# board.net
KiCad netlist of a schematic drawn in EAGLE
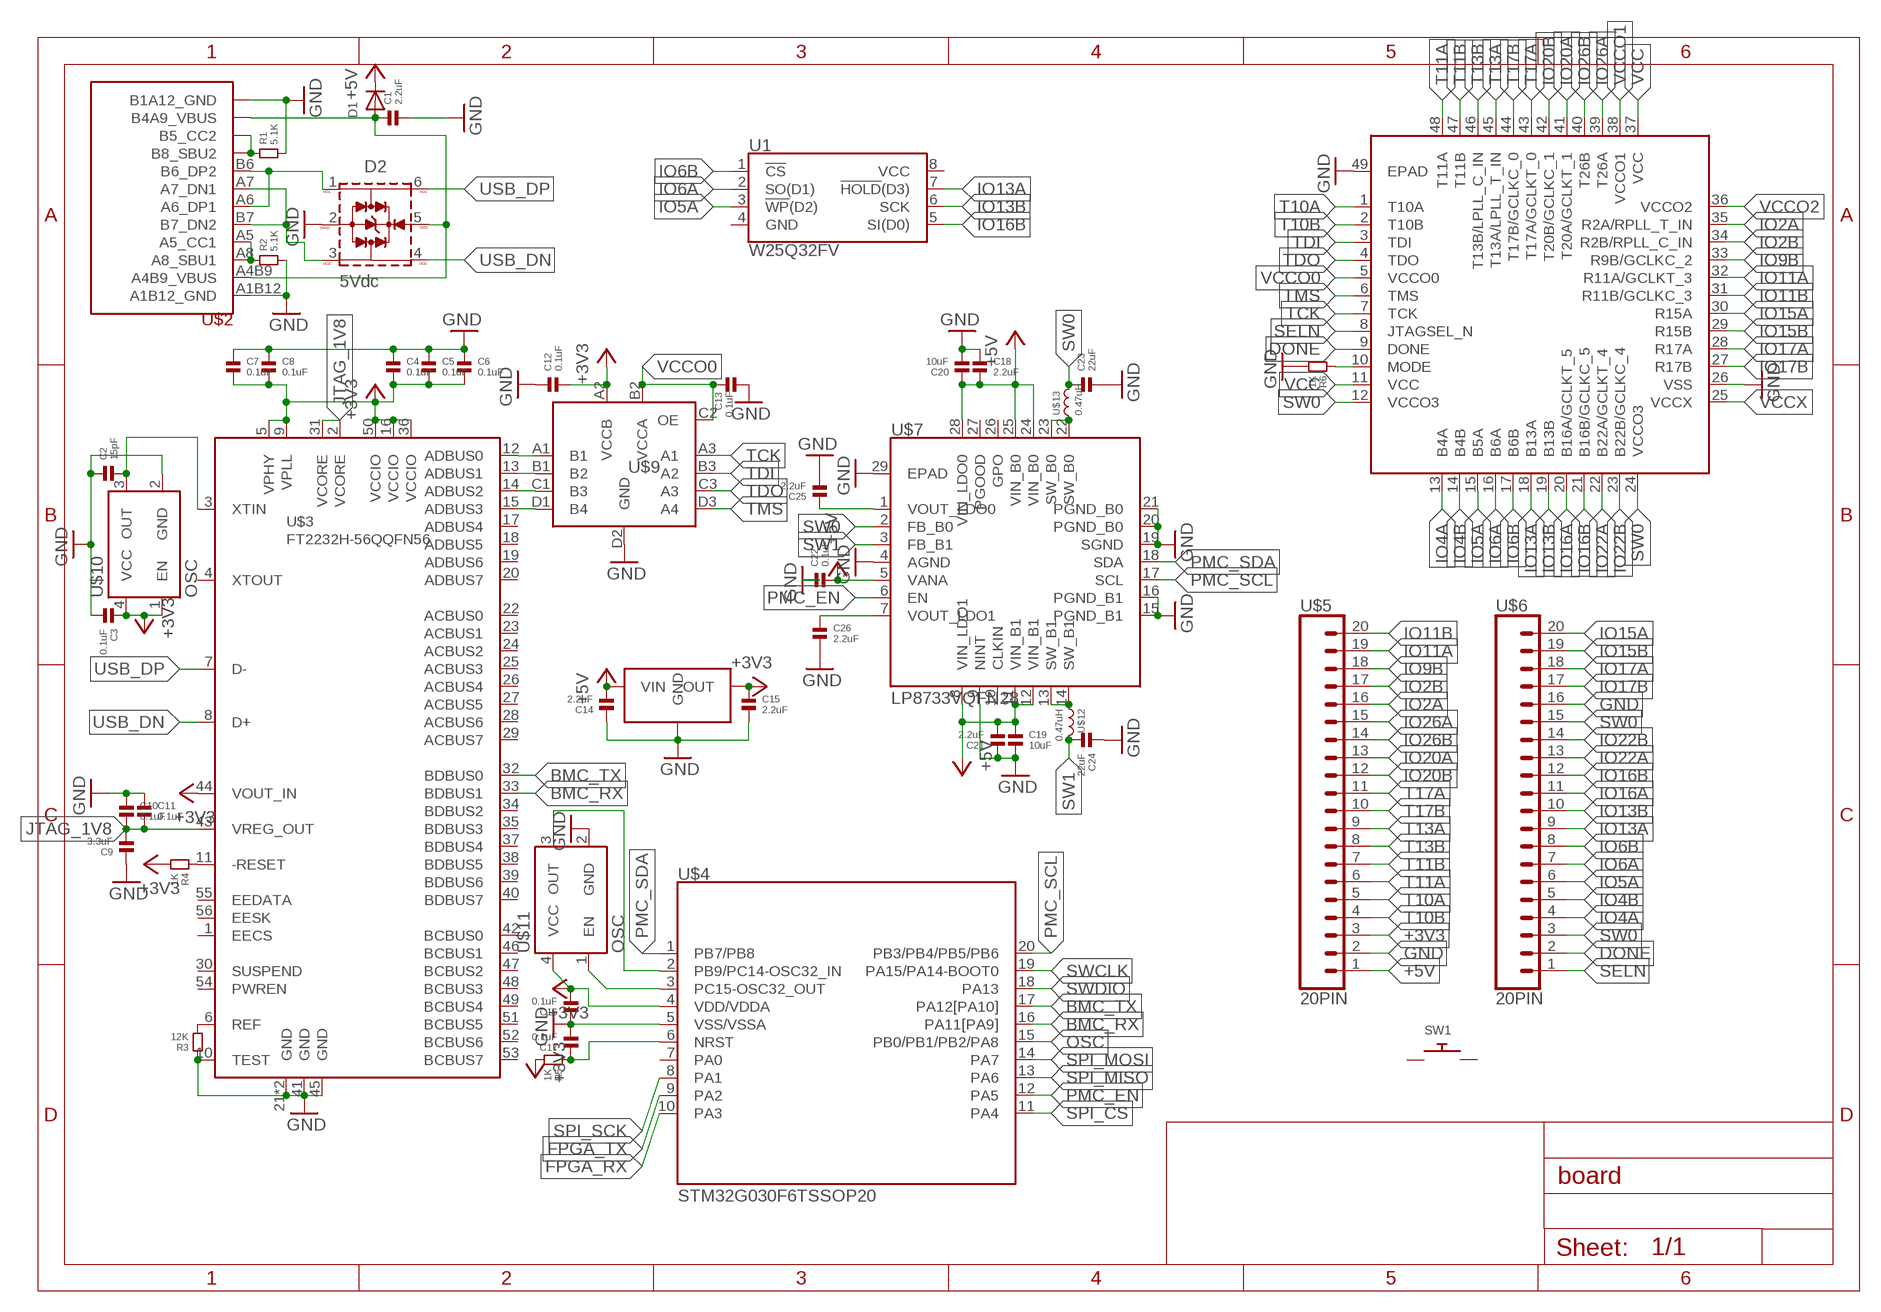
[diagram p0: schematic, sheet 1]

(export (version "E")
  (design (tool "Eeschema 10.0.6"))
  (components
    (comp (ref "C1")
      (value "2.2uF")
      (footprint "eagle-import:0603_CAP")
      (libsource (lib "eagle-import") (part "CAPACITOR0603"))
    )
    (comp (ref "C2")
      (value "15pF")
      (footprint "eagle-import:0402_CAP")
      (libsource (lib "eagle-import") (part "CAPACITOR"))
    )
    (comp (ref "C3")
      (value "0.1uF")
      (footprint "eagle-import:0402_CAP")
      (libsource (lib "eagle-import") (part "CAPACITOR"))
    )
    (comp (ref "C4")
      (value "0.1uF")
      (footprint "eagle-import:0402_CAP")
      (libsource (lib "eagle-import") (part "CAPACITOR"))
    )
    (comp (ref "C5")
      (value "0.1uF")
      (footprint "eagle-import:0402_CAP")
      (libsource (lib "eagle-import") (part "CAPACITOR"))
    )
    (comp (ref "C6")
      (value "0.1uF")
      (footprint "eagle-import:0402_CAP")
      (libsource (lib "eagle-import") (part "CAPACITOR"))
    )
    (comp (ref "C7")
      (value "0.1uF")
      (footprint "eagle-import:0402_CAP")
      (libsource (lib "eagle-import") (part "CAPACITOR"))
    )
    (comp (ref "C8")
      (value "0.1uF")
      (footprint "eagle-import:0402_CAP")
      (libsource (lib "eagle-import") (part "CAPACITOR"))
    )
    (comp (ref "C9")
      (value "3.3uF")
      (footprint "eagle-import:0603_CAP")
      (libsource (lib "eagle-import") (part "CAPACITOR0603"))
    )
    (comp (ref "C10")
      (value "0.1uF")
      (footprint "eagle-import:0402_CAP")
      (libsource (lib "eagle-import") (part "CAPACITOR"))
    )
    (comp (ref "C11")
      (value "0.1uF")
      (footprint "eagle-import:0402_CAP")
      (libsource (lib "eagle-import") (part "CAPACITOR"))
    )
    (comp (ref "C12")
      (value "0.1uF")
      (footprint "eagle-import:0402_CAP")
      (libsource (lib "eagle-import") (part "CAPACITOR"))
    )
    (comp (ref "C13")
      (value "0.1uF")
      (footprint "eagle-import:0402_CAP")
      (libsource (lib "eagle-import") (part "CAPACITOR"))
    )
    (comp (ref "C14")
      (value "2.2uF")
      (footprint "eagle-import:0603_CAP")
      (libsource (lib "eagle-import") (part "CAPACITOR0603"))
    )
    (comp (ref "C15")
      (value "2.2uF")
      (footprint "eagle-import:0603_CAP")
      (libsource (lib "eagle-import") (part "CAPACITOR0603"))
    )
    (comp (ref "C16")
      (value "0.1uF")
      (footprint "eagle-import:0402_CAP")
      (libsource (lib "eagle-import") (part "CAPACITOR"))
    )
    (comp (ref "C17")
      (value "0.1uF")
      (footprint "eagle-import:0402_CAP")
      (libsource (lib "eagle-import") (part "CAPACITOR"))
    )
    (comp (ref "C18")
      (value "2.2uF")
      (footprint "eagle-import:0603_CAP")
      (libsource (lib "eagle-import") (part "CAPACITOR0603"))
    )
    (comp (ref "C19")
      (value "10uF")
      (footprint "eagle-import:0805_CAP")
      (libsource (lib "eagle-import") (part "CAPACITOR0805"))
    )
    (comp (ref "C20")
      (value "10uF")
      (footprint "eagle-import:0805_CAP")
      (libsource (lib "eagle-import") (part "CAPACITOR0805"))
    )
    (comp (ref "C21")
      (value "2.2uF")
      (footprint "eagle-import:0603_CAP")
      (libsource (lib "eagle-import") (part "CAPACITOR0603"))
    )
    (comp (ref "C22")
      (value "0.1uF")
      (footprint "eagle-import:0402_CAP")
      (libsource (lib "eagle-import") (part "CAPACITOR"))
    )
    (comp (ref "C23")
      (value "22uF")
      (footprint "eagle-import:0805_CAP")
      (libsource (lib "eagle-import") (part "CAPACITOR0805"))
    )
    (comp (ref "C24")
      (value "22uF")
      (footprint "eagle-import:0805_CAP")
      (libsource (lib "eagle-import") (part "CAPACITOR0805"))
    )
    (comp (ref "C25")
      (value "2.2uF")
      (footprint "eagle-import:0603_CAP")
      (libsource (lib "eagle-import") (part "CAPACITOR0603"))
    )
    (comp (ref "C26")
      (value "2.2uF")
      (footprint "eagle-import:0603_CAP")
      (libsource (lib "eagle-import") (part "CAPACITOR0603"))
    )
    (comp (ref "D1")
      (value "DIODESOD-323F")
      (footprint "eagle-import:SOD-323F")
      (libsource (lib "eagle-import") (part "DIODESOD-323F"))
    )
    (comp (ref "D2")
      (value "5Vdc")
      (footprint "eagle-import:WE-TVS_SOT23-6L")
      (libsource (lib "eagle-import") (part "WE-TVS-HS_SOT23-6L_82400102"))
    )
    (comp (ref "R1")
      (value "5.1K")
      (footprint "eagle-import:0402")
      (libsource (lib "eagle-import") (part "RESISTOR.0402"))
    )
    (comp (ref "R2")
      (value "5.1K")
      (footprint "eagle-import:0402")
      (libsource (lib "eagle-import") (part "RESISTOR.0402"))
    )
    (comp (ref "R3")
      (value "12K")
      (footprint "eagle-import:0402")
      (libsource (lib "eagle-import") (part "RESISTOR.0402"))
    )
    (comp (ref "R4")
      (value "1K")
      (footprint "eagle-import:0402")
      (libsource (lib "eagle-import") (part "RESISTOR.0402"))
    )
    (comp (ref "R5")
      (value "1K")
      (footprint "eagle-import:0402")
      (libsource (lib "eagle-import") (part "RESISTOR.0402"))
    )
    (comp (ref "R6")
      (value "1K")
      (footprint "eagle-import:0402")
      (libsource (lib "eagle-import") (part "RESISTOR.0402"))
    )
    (comp (ref "SW1")
      (value "SWITCH_PUSHBUTTONC&K_KSS")
      (footprint "eagle-import:BTN_CK_KSS")
      (libsource (lib "eagle-import") (part "SWITCH_PUSHBUTTONC&K_KSS"))
    )
    (comp (ref "U$1")
      (value "GW1NSR-4CQN48P")
      (footprint "eagle-import:QFN40P600X600X80-49T420N")
      (libsource (lib "eagle-import") (part "GW1NSR-4CQN48P"))
    )
    (comp (ref "U$2")
      (value "TYPEC")
      (footprint "eagle-import:TYPE-C-31-M-12")
      (libsource (lib "eagle-import") (part "TYPEC"))
    )
    (comp (ref "U$3")
      (value "FT2232H-56QQFN56")
      (footprint "eagle-import:QFN50P800X800X90-57T595N")
      (libsource (lib "eagle-import") (part "FT2232H-56QQFN56"))
    )
    (comp (ref "U$4")
      (value "STM32G030F6TSSOP20")
      (footprint "eagle-import:SOP65P640X120-20N")
      (libsource (lib "eagle-import") (part "STM32G030F6TSSOP20"))
    )
    (comp (ref "U$5")
      (value "20PIN")
      (footprint "eagle-import:HDRV20W64P254_1X20_5080X254X838B")
      (libsource (lib "eagle-import") (part "120PIN"))
    )
    (comp (ref "U$6")
      (value "20PIN")
      (footprint "eagle-import:HDRV20W64P254_1X20_5080X254X838B")
      (libsource (lib "eagle-import") (part "120PIN"))
    )
    (comp (ref "U$7")
      (value "LP8733VQFN28")
      (footprint "eagle-import:QFN50P500X500X100-29T340N")
      (libsource (lib "eagle-import") (part "LP8733VQFN28"))
    )
    (comp (ref "U$8")
      (value "XC6206")
      (footprint "eagle-import:SOT95P280X125-3")
      (libsource (lib "eagle-import") (part "XC6206"))
    )
    (comp (ref "U$9")
      (value "TXS0104EYZTR")
      (footprint "eagle-import:BGA12C50P3X4_186X136X62N")
      (libsource (lib "eagle-import") (part "TXS0104EYZTR"))
    )
    (comp (ref "U$10")
      (value "OSC")
      (footprint "eagle-import:OSCCC200X160X85N")
      (libsource (lib "eagle-import") (part "OSC"))
    )
    (comp (ref "U$11")
      (value "OSC")
      (footprint "eagle-import:OSCCC200X160X85N")
      (libsource (lib "eagle-import") (part "OSC"))
    )
    (comp (ref "U$12")
      (value "0.47uH")
      (footprint "eagle-import:INDM2621X120")
      (libsource (lib "eagle-import") (part "SPH252012H1R5MT"))
    )
    (comp (ref "U$13")
      (value "0.47uH")
      (footprint "eagle-import:INDM2621X120")
      (libsource (lib "eagle-import") (part "SPH252012H1R5MT"))
    )
    (comp (ref "U1")
      (value "W25Q32FV")
      (footprint "eagle-import:SOIC-8")
      (libsource (lib "eagle-import") (part "GD25LQ128DVIG"))
    )
  )
  (nets
    (net (code "1") (name "+3V3") (class "Default")
      (node (ref "C12") (pin "2") (pinfunction "2_2") (pintype "bidirectional"))
      (node (ref "C15") (pin "1") (pinfunction "1_1") (pintype "bidirectional"))
      (node (ref "C16") (pin "2") (pinfunction "2_2") (pintype "bidirectional"))
      (node (ref "C3") (pin "1") (pinfunction "1_1") (pintype "bidirectional"))
      (node (ref "C4") (pin "2") (pinfunction "2_2") (pintype "bidirectional"))
      (node (ref "C5") (pin "2") (pinfunction "2_2") (pintype "bidirectional"))
      (node (ref "C6") (pin "2") (pinfunction "2_2") (pintype "bidirectional"))
      (node (ref "C7") (pin "2") (pinfunction "2_2") (pintype "bidirectional"))
      (node (ref "C8") (pin "2") (pinfunction "2_2") (pintype "bidirectional"))
      (node (ref "R4") (pin "2") (pinfunction "2_2") (pintype "bidirectional"))
      (node (ref "R5") (pin "2") (pinfunction "2_2") (pintype "bidirectional"))
      (node (ref "U$10") (pin "1") (pinfunction "EN_1") (pintype "bidirectional"))
      (node (ref "U$10") (pin "4") (pinfunction "VCC_4") (pintype "bidirectional"))
      (node (ref "U$11") (pin "4") (pinfunction "VCC_4") (pintype "bidirectional"))
      (node (ref "U$3") (pin "16") (pinfunction "VCCIO_16") (pintype "bidirectional"))
      (node (ref "U$3") (pin "36") (pinfunction "VCCIO_36") (pintype "bidirectional"))
      (node (ref "U$3") (pin "44") (pinfunction "VOUT_IN_44") (pintype "bidirectional"))
      (node (ref "U$3") (pin "5") (pinfunction "VPHY_5") (pintype "bidirectional"))
      (node (ref "U$3") (pin "50") (pinfunction "VCCIO_50") (pintype "bidirectional"))
      (node (ref "U$3") (pin "9") (pinfunction "VPLL_9") (pintype "bidirectional"))
      (node (ref "U$4") (pin "4") (pinfunction "VDD/VDDA_4") (pintype "bidirectional"))
      (node (ref "U$5") (pin "3") (pinfunction "3_3") (pintype "passive"))
      (node (ref "U$8") (pin "2") (pinfunction "OUT_2") (pintype "bidirectional"))
      (node (ref "U$9") (pin "A2") (pinfunction "VCCB_A2") (pintype "bidirectional"))
    )
    (net (code "2") (name "+5V") (class "Default")
      (node (ref "C14") (pin "2") (pinfunction "2_2") (pintype "bidirectional"))
      (node (ref "C18") (pin "2") (pinfunction "2_2") (pintype "bidirectional"))
      (node (ref "C19") (pin "1") (pinfunction "1_1") (pintype "bidirectional"))
      (node (ref "C20") (pin "1") (pinfunction "1_1") (pintype "bidirectional"))
      (node (ref "C21") (pin "2") (pinfunction "2_2") (pintype "bidirectional"))
      (node (ref "C22") (pin "2") (pinfunction "2_2") (pintype "bidirectional"))
      (node (ref "D1") (pin "C") (pinfunction "C_C") (pintype "passive"))
      (node (ref "U$5") (pin "1") (pinfunction "1_1") (pintype "passive"))
      (node (ref "U$7") (pin "11") (pinfunction "VIN_B1_11") (pintype "bidirectional"))
      (node (ref "U$7") (pin "12") (pinfunction "VIN_B1_12") (pintype "bidirectional"))
      (node (ref "U$7") (pin "24") (pinfunction "VIN_B0_24") (pintype "bidirectional"))
      (node (ref "U$7") (pin "25") (pinfunction "VIN_B0_25") (pintype "bidirectional"))
      (node (ref "U$7") (pin "28") (pinfunction "VIN_LDO0_28") (pintype "bidirectional"))
      (node (ref "U$7") (pin "5") (pinfunction "VANA_5") (pintype "bidirectional"))
      (node (ref "U$7") (pin "8") (pinfunction "VIN_LDO1_8") (pintype "bidirectional"))
      (node (ref "U$8") (pin "3") (pinfunction "VIN_3") (pintype "bidirectional"))
    )
    (net (code "3") (name "BMC_RX") (class "Default")
      (node (ref "U$3") (pin "33") (pinfunction "BDBUS1_33") (pintype "bidirectional"))
      (node (ref "U$4") (pin "16") (pinfunction "PA11[PA9]_16") (pintype "bidirectional"))
    )
    (net (code "4") (name "BMC_TX") (class "Default")
      (node (ref "U$3") (pin "32") (pinfunction "BDBUS0_32") (pintype "bidirectional"))
      (node (ref "U$4") (pin "17") (pinfunction "PA12[PA10]_17") (pintype "bidirectional"))
    )
    (net (code "5") (name "DONE") (class "Default")
      (node (ref "U$1") (pin "9") (pinfunction "DONE_9") (pintype "bidirectional"))
      (node (ref "U$6") (pin "2") (pinfunction "2_2") (pintype "passive"))
    )
    (net (code "6") (name "FPGA_RX") (class "Default")
      (node (ref "U$4") (pin "10") (pinfunction "PA3_10") (pintype "bidirectional"))
    )
    (net (code "7") (name "FPGA_TX") (class "Default")
      (node (ref "U$4") (pin "9") (pinfunction "PA2_9") (pintype "bidirectional"))
    )
    (net (code "8") (name "GND") (class "Default")
      (node (ref "C1") (pin "2") (pinfunction "2_2") (pintype "bidirectional"))
      (node (ref "C10") (pin "1") (pinfunction "1_1") (pintype "bidirectional"))
      (node (ref "C11") (pin "1") (pinfunction "1_1") (pintype "bidirectional"))
      (node (ref "C12") (pin "1") (pinfunction "1_1") (pintype "bidirectional"))
      (node (ref "C13") (pin "2") (pinfunction "2_2") (pintype "bidirectional"))
      (node (ref "C14") (pin "1") (pinfunction "1_1") (pintype "bidirectional"))
      (node (ref "C15") (pin "2") (pinfunction "2_2") (pintype "bidirectional"))
      (node (ref "C16") (pin "1") (pinfunction "1_1") (pintype "bidirectional"))
      (node (ref "C17") (pin "2") (pinfunction "2_2") (pintype "bidirectional"))
      (node (ref "C18") (pin "1") (pinfunction "1_1") (pintype "bidirectional"))
      (node (ref "C19") (pin "2") (pinfunction "2_2") (pintype "bidirectional"))
      (node (ref "C2") (pin "1") (pinfunction "1_1") (pintype "bidirectional"))
      (node (ref "C20") (pin "2") (pinfunction "2_2") (pintype "bidirectional"))
      (node (ref "C21") (pin "1") (pinfunction "1_1") (pintype "bidirectional"))
      (node (ref "C22") (pin "1") (pinfunction "1_1") (pintype "bidirectional"))
      (node (ref "C23") (pin "2") (pinfunction "2_2") (pintype "bidirectional"))
      (node (ref "C24") (pin "1") (pinfunction "1_1") (pintype "bidirectional"))
      (node (ref "C25") (pin "2") (pinfunction "2_2") (pintype "bidirectional"))
      (node (ref "C26") (pin "2") (pinfunction "2_2") (pintype "bidirectional"))
      (node (ref "C3") (pin "2") (pinfunction "2_2") (pintype "bidirectional"))
      (node (ref "C4") (pin "1") (pinfunction "1_1") (pintype "bidirectional"))
      (node (ref "C5") (pin "1") (pinfunction "1_1") (pintype "bidirectional"))
      (node (ref "C6") (pin "1") (pinfunction "1_1") (pintype "bidirectional"))
      (node (ref "C7") (pin "1") (pinfunction "1_1") (pintype "bidirectional"))
      (node (ref "C8") (pin "1") (pinfunction "1_1") (pintype "bidirectional"))
      (node (ref "C9") (pin "1") (pinfunction "1_1") (pintype "bidirectional"))
      (node (ref "D2") (pin "2") (pinfunction "GND_2") (pintype "passive"))
      (node (ref "R1") (pin "2") (pinfunction "2_2") (pintype "bidirectional"))
      (node (ref "R2") (pin "2") (pinfunction "2_2") (pintype "bidirectional"))
      (node (ref "R3") (pin "1") (pinfunction "1_1") (pintype "bidirectional"))
      (node (ref "R6") (pin "2") (pinfunction "2_2") (pintype "bidirectional"))
      (node (ref "U$1") (pin "26") (pinfunction "VSS_26") (pintype "bidirectional"))
      (node (ref "U$1") (pin "49") (pinfunction "EPAD_49") (pintype "bidirectional"))
      (node (ref "U$10") (pin "2") (pinfunction "GND_2") (pintype "bidirectional"))
      (node (ref "U$11") (pin "2") (pinfunction "GND_2") (pintype "bidirectional"))
      (node (ref "U$2") (pin "A1B12") (pinfunction "A1B12_GND_A1B12") (pintype "bidirectional"))
      (node (ref "U$2") (pin "B1A12") (pinfunction "B1A12_GND_B1A12") (pintype "bidirectional"))
      (node (ref "U$3") (pin "10") (pinfunction "TEST_10") (pintype "bidirectional"))
      (node (ref "U$3") (pin "21") (pinfunction "GND_21") (pintype "power_in"))
      (node (ref "U$3") (pin "41") (pinfunction "GND_41") (pintype "power_in"))
      (node (ref "U$3") (pin "45") (pinfunction "GND_45") (pintype "power_in"))
      (node (ref "U$3") (pin "57") (pinfunction "GND_57") (pintype "power_in"))
      (node (ref "U$4") (pin "5") (pinfunction "VSS/VSSA_5") (pintype "bidirectional"))
      (node (ref "U$5") (pin "2") (pinfunction "2_2") (pintype "passive"))
      (node (ref "U$6") (pin "16") (pinfunction "16_16") (pintype "passive"))
      (node (ref "U$7") (pin "15") (pinfunction "PGND_B1_15") (pintype "bidirectional"))
      (node (ref "U$7") (pin "16") (pinfunction "PGND_B1_16") (pintype "bidirectional"))
      (node (ref "U$7") (pin "19") (pinfunction "SGND_19") (pintype "bidirectional"))
      (node (ref "U$7") (pin "20") (pinfunction "PGND_B0_20") (pintype "bidirectional"))
      (node (ref "U$7") (pin "21") (pinfunction "PGND_B0_21") (pintype "bidirectional"))
      (node (ref "U$7") (pin "29") (pinfunction "EPAD_29") (pintype "bidirectional"))
      (node (ref "U$7") (pin "4") (pinfunction "AGND_4") (pintype "bidirectional"))
      (node (ref "U$7") (pin "9") (pinfunction "NINT_9") (pintype "bidirectional"))
      (node (ref "U$8") (pin "1") (pinfunction "GND_1") (pintype "bidirectional"))
      (node (ref "U$9") (pin "D2") (pinfunction "GND_D2") (pintype "bidirectional"))
    )
    (net (code "9") (name "IO2A") (class "Default")
      (node (ref "U$1") (pin "35") (pinfunction "R2A/RPLL_T_IN_35") (pintype "bidirectional"))
      (node (ref "U$5") (pin "16") (pinfunction "16_16") (pintype "passive"))
    )
    (net (code "10") (name "IO2B") (class "Default")
      (node (ref "U$1") (pin "34") (pinfunction "R2B/RPLL_C_IN_34") (pintype "bidirectional"))
      (node (ref "U$5") (pin "17") (pinfunction "17_17") (pintype "passive"))
    )
    (net (code "11") (name "IO4A") (class "Default")
      (node (ref "U$1") (pin "13") (pinfunction "B4A_13") (pintype "bidirectional"))
      (node (ref "U$6") (pin "4") (pinfunction "4_4") (pintype "passive"))
    )
    (net (code "12") (name "IO4B") (class "Default")
      (node (ref "U$1") (pin "14") (pinfunction "B4B_14") (pintype "bidirectional"))
      (node (ref "U$6") (pin "5") (pinfunction "5_5") (pintype "passive"))
    )
    (net (code "13") (name "IO5A") (class "Default")
      (node (ref "U$1") (pin "15") (pinfunction "B5A_15") (pintype "bidirectional"))
      (node (ref "U$6") (pin "6") (pinfunction "6_6") (pintype "passive"))
      (node (ref "U1") (pin "3") (pinfunction "~{WP}(D2)_3") (pintype "bidirectional"))
    )
    (net (code "14") (name "IO6A") (class "Default")
      (node (ref "U$1") (pin "16") (pinfunction "B6A_16") (pintype "bidirectional"))
      (node (ref "U$6") (pin "7") (pinfunction "7_7") (pintype "passive"))
      (node (ref "U1") (pin "2") (pinfunction "SO(D1)_2") (pintype "bidirectional"))
    )
    (net (code "15") (name "IO6B") (class "Default")
      (node (ref "U$1") (pin "17") (pinfunction "B6B_17") (pintype "bidirectional"))
      (node (ref "U$6") (pin "8") (pinfunction "8_8") (pintype "passive"))
      (node (ref "U1") (pin "1") (pinfunction "~{CS}_1") (pintype "bidirectional"))
    )
    (net (code "16") (name "IO9B") (class "Default")
      (node (ref "U$1") (pin "33") (pinfunction "R9B/GCLKC_2_33") (pintype "bidirectional"))
      (node (ref "U$5") (pin "18") (pinfunction "18_18") (pintype "passive"))
    )
    (net (code "17") (name "IO11A") (class "Default")
      (node (ref "U$1") (pin "32") (pinfunction "R11A/GCLKT_3_32") (pintype "bidirectional"))
      (node (ref "U$5") (pin "19") (pinfunction "19_19") (pintype "passive"))
    )
    (net (code "18") (name "IO11B") (class "Default")
      (node (ref "U$1") (pin "31") (pinfunction "R11B/GCLKC_3_31") (pintype "bidirectional"))
      (node (ref "U$5") (pin "20") (pinfunction "20_20") (pintype "passive"))
    )
    (net (code "19") (name "IO13A") (class "Default")
      (node (ref "U$1") (pin "18") (pinfunction "B13A_18") (pintype "bidirectional"))
      (node (ref "U$6") (pin "9") (pinfunction "9_9") (pintype "passive"))
      (node (ref "U1") (pin "7") (pinfunction "~{HOLD}(D3)_7") (pintype "bidirectional"))
    )
    (net (code "20") (name "IO13B") (class "Default")
      (node (ref "U$1") (pin "19") (pinfunction "B13B_19") (pintype "bidirectional"))
      (node (ref "U$6") (pin "10") (pinfunction "10_10") (pintype "passive"))
      (node (ref "U1") (pin "6") (pinfunction "SCK_6") (pintype "bidirectional"))
    )
    (net (code "21") (name "IO15A") (class "Default")
      (node (ref "U$1") (pin "30") (pinfunction "R15A_30") (pintype "bidirectional"))
      (node (ref "U$6") (pin "20") (pinfunction "20_20") (pintype "passive"))
    )
    (net (code "22") (name "IO15B") (class "Default")
      (node (ref "U$1") (pin "29") (pinfunction "R15B_29") (pintype "bidirectional"))
      (node (ref "U$6") (pin "19") (pinfunction "19_19") (pintype "passive"))
    )
    (net (code "23") (name "IO16A") (class "Default")
      (node (ref "U$1") (pin "20") (pinfunction "B16A/GCLKT_5_20") (pintype "bidirectional"))
      (node (ref "U$6") (pin "11") (pinfunction "11_11") (pintype "passive"))
    )
    (net (code "24") (name "IO16B") (class "Default")
      (node (ref "U$1") (pin "21") (pinfunction "B16B/GCLKC_5_21") (pintype "bidirectional"))
      (node (ref "U$6") (pin "12") (pinfunction "12_12") (pintype "passive"))
      (node (ref "U1") (pin "5") (pinfunction "SI(D0)_5") (pintype "bidirectional"))
    )
    (net (code "25") (name "IO17A") (class "Default")
      (node (ref "U$1") (pin "28") (pinfunction "R17A_28") (pintype "bidirectional"))
      (node (ref "U$6") (pin "18") (pinfunction "18_18") (pintype "passive"))
    )
    (net (code "26") (name "IO17B") (class "Default")
      (node (ref "U$1") (pin "27") (pinfunction "R17B_27") (pintype "bidirectional"))
      (node (ref "U$6") (pin "17") (pinfunction "17_17") (pintype "passive"))
    )
    (net (code "27") (name "IO20A") (class "Default")
      (node (ref "U$1") (pin "41") (pinfunction "T20A/GCLKT_1_41") (pintype "bidirectional"))
      (node (ref "U$5") (pin "13") (pinfunction "13_13") (pintype "passive"))
    )
    (net (code "28") (name "IO20B") (class "Default")
      (node (ref "U$1") (pin "42") (pinfunction "T20B/GCLKC_1_42") (pintype "bidirectional"))
      (node (ref "U$5") (pin "12") (pinfunction "12_12") (pintype "passive"))
    )
    (net (code "29") (name "IO22A") (class "Default")
      (node (ref "U$1") (pin "22") (pinfunction "B22A/GCLKT_4_22") (pintype "bidirectional"))
      (node (ref "U$6") (pin "13") (pinfunction "13_13") (pintype "passive"))
    )
    (net (code "30") (name "IO22B") (class "Default")
      (node (ref "U$1") (pin "23") (pinfunction "B22B/GCLKC_4_23") (pintype "bidirectional"))
      (node (ref "U$6") (pin "14") (pinfunction "14_14") (pintype "passive"))
    )
    (net (code "31") (name "IO26A") (class "Default")
      (node (ref "U$1") (pin "39") (pinfunction "T26A_39") (pintype "bidirectional"))
      (node (ref "U$5") (pin "15") (pinfunction "15_15") (pintype "passive"))
    )
    (net (code "32") (name "IO26B") (class "Default")
      (node (ref "U$1") (pin "40") (pinfunction "T26B_40") (pintype "bidirectional"))
      (node (ref "U$5") (pin "14") (pinfunction "14_14") (pintype "passive"))
    )
    (net (code "33") (name "JTAG_1V8") (class "Default")
      (node (ref "C10") (pin "2") (pinfunction "2_2") (pintype "bidirectional"))
      (node (ref "C11") (pin "2") (pinfunction "2_2") (pintype "bidirectional"))
      (node (ref "C9") (pin "2") (pinfunction "2_2") (pintype "bidirectional"))
      (node (ref "U$3") (pin "2") (pinfunction "VCORE_2") (pintype "bidirectional"))
      (node (ref "U$3") (pin "31") (pinfunction "VCORE_31") (pintype "bidirectional"))
      (node (ref "U$3") (pin "43") (pinfunction "VREG_OUT_43") (pintype "output"))
    )
    (net (code "34") (name "Net-(D2-I{slash}O1)") (class "Default")
      (node (ref "D2") (pin "1") (pinfunction "I/O1_1") (pintype "passive"))
      (node (ref "U$2") (pin "A6") (pinfunction "A6_DP1_A6") (pintype "bidirectional"))
      (node (ref "U$2") (pin "B6") (pinfunction "B6_DP2_B6") (pintype "bidirectional"))
    )
    (net (code "35") (name "Net-(D2-I{slash}O2)") (class "Default")
      (node (ref "D2") (pin "3") (pinfunction "I/O2_3") (pintype "passive"))
      (node (ref "U$2") (pin "A7") (pinfunction "A7_DN1_A7") (pintype "bidirectional"))
      (node (ref "U$2") (pin "B7") (pinfunction "B7_DN2_B7") (pintype "bidirectional"))
    )
    (net (code "36") (name "Net-(D2-VDD)") (class "Default")
      (node (ref "C1") (pin "1") (pinfunction "1_1") (pintype "bidirectional"))
      (node (ref "D1") (pin "A") (pinfunction "A_A") (pintype "passive"))
      (node (ref "D2") (pin "5") (pinfunction "VDD_5") (pintype "passive"))
      (node (ref "U$2") (pin "A4B9") (pinfunction "A4B9_VBUS_A4B9") (pintype "bidirectional"))
      (node (ref "U$2") (pin "B4A9") (pinfunction "B4A9_VBUS_B4A9") (pintype "bidirectional"))
    )
    (net (code "37") (name "Net-(U$1-MODE)") (class "Default")
      (node (ref "R6") (pin "1") (pinfunction "1_1") (pintype "bidirectional"))
      (node (ref "U$1") (pin "10") (pinfunction "MODE_10") (pintype "bidirectional"))
    )
    (net (code "38") (name "Net-(U$2-A5_CC1)") (class "Default")
      (node (ref "R2") (pin "1") (pinfunction "1_1") (pintype "bidirectional"))
      (node (ref "U$2") (pin "A5") (pinfunction "A5_CC1_A5") (pintype "bidirectional"))
      (node (ref "U$2") (pin "A8") (pinfunction "A8_SBU1_A8") (pintype "bidirectional"))
    )
    (net (code "39") (name "Net-(U$2-B5_CC2)") (class "Default")
      (node (ref "R1") (pin "1") (pinfunction "1_1") (pintype "bidirectional"))
      (node (ref "U$2") (pin "B5") (pinfunction "B5_CC2_B5") (pintype "bidirectional"))
      (node (ref "U$2") (pin "B8") (pinfunction "B8_SBU2_B8") (pintype "bidirectional"))
    )
    (net (code "40") (name "Net-(U$3--RESET)") (class "Default")
      (node (ref "R4") (pin "1") (pinfunction "1_1") (pintype "bidirectional"))
      (node (ref "U$3") (pin "11") (pinfunction "-RESET_11") (pintype "input"))
    )
    (net (code "41") (name "Net-(U$3-ADBUS0)") (class "Default")
      (node (ref "U$3") (pin "12") (pinfunction "ADBUS0_12") (pintype "bidirectional"))
      (node (ref "U$9") (pin "A1") (pinfunction "B1_A1") (pintype "bidirectional"))
    )
    (net (code "42") (name "Net-(U$3-ADBUS1)") (class "Default")
      (node (ref "U$3") (pin "13") (pinfunction "ADBUS1_13") (pintype "bidirectional"))
      (node (ref "U$9") (pin "B1") (pinfunction "B2_B1") (pintype "bidirectional"))
    )
    (net (code "43") (name "Net-(U$3-ADBUS2)") (class "Default")
      (node (ref "U$3") (pin "14") (pinfunction "ADBUS2_14") (pintype "bidirectional"))
      (node (ref "U$9") (pin "C1") (pinfunction "B3_C1") (pintype "bidirectional"))
    )
    (net (code "44") (name "Net-(U$3-ADBUS3)") (class "Default")
      (node (ref "U$3") (pin "15") (pinfunction "ADBUS3_15") (pintype "bidirectional"))
      (node (ref "U$9") (pin "D1") (pinfunction "B4_D1") (pintype "bidirectional"))
    )
    (net (code "45") (name "Net-(U$3-REF)") (class "Default")
      (node (ref "R3") (pin "2") (pinfunction "2_2") (pintype "bidirectional"))
      (node (ref "U$3") (pin "6") (pinfunction "REF_6") (pintype "bidirectional"))
    )
    (net (code "46") (name "Net-(U$4-NRST)") (class "Default")
      (node (ref "C17") (pin "1") (pinfunction "1_1") (pintype "bidirectional"))
      (node (ref "R5") (pin "1") (pinfunction "1_1") (pintype "bidirectional"))
      (node (ref "U$4") (pin "6") (pinfunction "NRST_6") (pintype "bidirectional"))
    )
    (net (code "47") (name "Net-(U$7-VOUT_LDO0)") (class "Default")
      (node (ref "C25") (pin "1") (pinfunction "1_1") (pintype "bidirectional"))
      (node (ref "U$7") (pin "1") (pinfunction "VOUT_LDO0_1") (pintype "bidirectional"))
    )
    (net (code "48") (name "Net-(U$7-VOUT_LDO1)") (class "Default")
      (node (ref "C26") (pin "1") (pinfunction "1_1") (pintype "bidirectional"))
      (node (ref "U$7") (pin "7") (pinfunction "VOUT_LDO1_7") (pintype "bidirectional"))
    )
    (net (code "49") (name "Net-(U$10-OUT)") (class "Default")
      (node (ref "C2") (pin "2") (pinfunction "2_2") (pintype "bidirectional"))
      (node (ref "U$10") (pin "3") (pinfunction "OUT_3") (pintype "bidirectional"))
      (node (ref "U$3") (pin "3") (pinfunction "XTIN_3") (pintype "input"))
    )
    (net (code "50") (name "Net-(U$11-EN)") (class "Default")
      (node (ref "U$11") (pin "1") (pinfunction "EN_1") (pintype "bidirectional"))
      (node (ref "U$4") (pin "3") (pinfunction "PC15-OSC32_OUT_3") (pintype "bidirectional"))
    )
    (net (code "51") (name "Net-(U$11-OUT)") (class "Default")
      (node (ref "U$11") (pin "3") (pinfunction "OUT_3") (pintype "bidirectional"))
      (node (ref "U$4") (pin "2") (pinfunction "PB9/PC14-OSC32_IN_2") (pintype "bidirectional"))
    )
    (net (code "52") (name "Net-(U$12-Pad1)") (class "Default")
      (node (ref "U$12") (pin "1") (pinfunction "1_1") (pintype "passive"))
      (node (ref "U$7") (pin "13") (pinfunction "SW_B1_13") (pintype "bidirectional"))
      (node (ref "U$7") (pin "14") (pinfunction "SW_B1_14") (pintype "bidirectional"))
    )
    (net (code "53") (name "Net-(U$13-Pad1)") (class "Default")
      (node (ref "U$13") (pin "1") (pinfunction "1_1") (pintype "passive"))
      (node (ref "U$7") (pin "22") (pinfunction "SW_B0_22") (pintype "bidirectional"))
      (node (ref "U$7") (pin "23") (pinfunction "SW_B0_23") (pintype "bidirectional"))
    )
    (net (code "54") (name "OSC") (class "Default")
      (node (ref "U$4") (pin "15") (pinfunction "PB0/PB1/PB2/PA8_15") (pintype "bidirectional"))
    )
    (net (code "55") (name "PMC_EN") (class "Default")
      (node (ref "U$4") (pin "12") (pinfunction "PA5_12") (pintype "bidirectional"))
      (node (ref "U$7") (pin "6") (pinfunction "EN_6") (pintype "bidirectional"))
    )
    (net (code "56") (name "PMC_SCL") (class "Default")
      (node (ref "U$4") (pin "20") (pinfunction "PB3/PB4/PB5/PB6_20") (pintype "bidirectional"))
      (node (ref "U$7") (pin "17") (pinfunction "SCL_17") (pintype "bidirectional"))
    )
    (net (code "57") (name "PMC_SDA") (class "Default")
      (node (ref "U$4") (pin "1") (pinfunction "PB7/PB8_1") (pintype "bidirectional"))
      (node (ref "U$7") (pin "18") (pinfunction "SDA_18") (pintype "bidirectional"))
    )
    (net (code "58") (name "SELN") (class "Default")
      (node (ref "U$1") (pin "8") (pinfunction "JTAGSEL_N_8") (pintype "bidirectional"))
      (node (ref "U$6") (pin "1") (pinfunction "1_1") (pintype "passive"))
    )
    (net (code "59") (name "SPI_CS") (class "Default")
      (node (ref "U$4") (pin "11") (pinfunction "PA4_11") (pintype "bidirectional"))
    )
    (net (code "60") (name "SPI_MISO") (class "Default")
      (node (ref "U$4") (pin "13") (pinfunction "PA6_13") (pintype "bidirectional"))
    )
    (net (code "61") (name "SPI_MOSI") (class "Default")
      (node (ref "U$4") (pin "14") (pinfunction "PA7_14") (pintype "bidirectional"))
    )
    (net (code "62") (name "SPI_SCK") (class "Default")
      (node (ref "U$4") (pin "8") (pinfunction "PA1_8") (pintype "bidirectional"))
    )
    (net (code "63") (name "SW0") (class "Default")
      (node (ref "C23") (pin "1") (pinfunction "1_1") (pintype "bidirectional"))
      (node (ref "U$1") (pin "12") (pinfunction "VCCO3_12") (pintype "bidirectional"))
      (node (ref "U$1") (pin "24") (pinfunction "VCCO3_24") (pintype "bidirectional"))
      (node (ref "U$13") (pin "2") (pinfunction "2_2") (pintype "passive"))
      (node (ref "U$6") (pin "15") (pinfunction "15_15") (pintype "passive"))
      (node (ref "U$6") (pin "3") (pinfunction "3_3") (pintype "passive"))
      (node (ref "U$7") (pin "2") (pinfunction "FB_B0_2") (pintype "bidirectional"))
    )
    (net (code "64") (name "SW1") (class "Default")
      (node (ref "C24") (pin "2") (pinfunction "2_2") (pintype "bidirectional"))
      (node (ref "U$12") (pin "2") (pinfunction "2_2") (pintype "passive"))
      (node (ref "U$7") (pin "3") (pinfunction "FB_B1_3") (pintype "bidirectional"))
    )
    (net (code "65") (name "SWCLK") (class "Default")
      (node (ref "U$4") (pin "19") (pinfunction "PA15/PA14-BOOT0_19") (pintype "bidirectional"))
    )
    (net (code "66") (name "SWDIO") (class "Default")
      (node (ref "U$4") (pin "18") (pinfunction "PA13_18") (pintype "bidirectional"))
    )
    (net (code "67") (name "T10A") (class "Default")
      (node (ref "U$1") (pin "1") (pinfunction "T10A_1") (pintype "bidirectional"))
      (node (ref "U$5") (pin "5") (pinfunction "5_5") (pintype "passive"))
    )
    (net (code "68") (name "T10B") (class "Default")
      (node (ref "U$1") (pin "2") (pinfunction "T10B_2") (pintype "bidirectional"))
      (node (ref "U$5") (pin "4") (pinfunction "4_4") (pintype "passive"))
    )
    (net (code "69") (name "T11A") (class "Default")
      (node (ref "U$1") (pin "48") (pinfunction "T11A_48") (pintype "bidirectional"))
      (node (ref "U$5") (pin "6") (pinfunction "6_6") (pintype "passive"))
    )
    (net (code "70") (name "T11B") (class "Default")
      (node (ref "U$1") (pin "47") (pinfunction "T11B_47") (pintype "bidirectional"))
      (node (ref "U$5") (pin "7") (pinfunction "7_7") (pintype "passive"))
    )
    (net (code "71") (name "T13A") (class "Default")
      (node (ref "U$1") (pin "45") (pinfunction "T13A/LPLL_T_IN_45") (pintype "bidirectional"))
      (node (ref "U$5") (pin "9") (pinfunction "9_9") (pintype "passive"))
    )
    (net (code "72") (name "T13B") (class "Default")
      (node (ref "U$1") (pin "46") (pinfunction "T13B/LPLL_C_IN_46") (pintype "bidirectional"))
      (node (ref "U$5") (pin "8") (pinfunction "8_8") (pintype "passive"))
    )
    (net (code "73") (name "T17A") (class "Default")
      (node (ref "U$1") (pin "43") (pinfunction "T17A/GCLKT_0_43") (pintype "bidirectional"))
      (node (ref "U$5") (pin "11") (pinfunction "11_11") (pintype "passive"))
    )
    (net (code "74") (name "T17B") (class "Default")
      (node (ref "U$1") (pin "44") (pinfunction "T17B/GCLKC_0_44") (pintype "bidirectional"))
      (node (ref "U$5") (pin "10") (pinfunction "10_10") (pintype "passive"))
    )
    (net (code "75") (name "TCK") (class "Default")
      (node (ref "U$1") (pin "7") (pinfunction "TCK_7") (pintype "bidirectional"))
      (node (ref "U$9") (pin "A3") (pinfunction "A1_A3") (pintype "bidirectional"))
    )
    (net (code "76") (name "TDI") (class "Default")
      (node (ref "U$1") (pin "3") (pinfunction "TDI_3") (pintype "bidirectional"))
      (node (ref "U$9") (pin "B3") (pinfunction "A2_B3") (pintype "bidirectional"))
    )
    (net (code "77") (name "TDO") (class "Default")
      (node (ref "U$1") (pin "4") (pinfunction "TDO_4") (pintype "bidirectional"))
      (node (ref "U$9") (pin "C3") (pinfunction "A3_C3") (pintype "bidirectional"))
    )
    (net (code "78") (name "TMS") (class "Default")
      (node (ref "U$1") (pin "6") (pinfunction "TMS_6") (pintype "bidirectional"))
      (node (ref "U$9") (pin "D3") (pinfunction "A4_D3") (pintype "bidirectional"))
    )
    (net (code "79") (name "USB_DN") (class "Default")
      (node (ref "D2") (pin "4") (pinfunction "I/O4_4") (pintype "passive"))
      (node (ref "U$3") (pin "8") (pinfunction "D+_8") (pintype "bidirectional"))
    )
    (net (code "80") (name "USB_DP") (class "Default")
      (node (ref "D2") (pin "6") (pinfunction "I/O3_6") (pintype "passive"))
      (node (ref "U$3") (pin "7") (pinfunction "D-_7") (pintype "bidirectional"))
    )
    (net (code "81") (name "VCC") (class "Default")
      (node (ref "U$1") (pin "11") (pinfunction "VCC_11") (pintype "bidirectional"))
      (node (ref "U$1") (pin "37") (pinfunction "VCC_37") (pintype "bidirectional"))
    )
    (net (code "82") (name "VCCO0") (class "Default")
      (node (ref "C13") (pin "1") (pinfunction "1_1") (pintype "bidirectional"))
      (node (ref "U$1") (pin "5") (pinfunction "VCCO0_5") (pintype "bidirectional"))
      (node (ref "U$9") (pin "B2") (pinfunction "VCCA_B2") (pintype "bidirectional"))
      (node (ref "U$9") (pin "C2") (pinfunction "OE_C2") (pintype "bidirectional"))
    )
    (net (code "83") (name "VCCO1") (class "Default")
      (node (ref "U$1") (pin "38") (pinfunction "VCCO1_38") (pintype "bidirectional"))
    )
    (net (code "84") (name "VCCO2") (class "Default")
      (node (ref "U$1") (pin "36") (pinfunction "VCCO2_36") (pintype "bidirectional"))
    )
    (net (code "85") (name "VCCX") (class "Default")
      (node (ref "U$1") (pin "25") (pinfunction "VCCX_25") (pintype "bidirectional"))
    )
    (net (code "86") (name "unconnected-(SW1-PadP$1)") (class "Default")
      (node (ref "SW1") (pin "P$1") (pinfunction "P$1_P$1") (pintype "passive"))
    )
    (net (code "87") (name "unconnected-(SW1-PadP$2)") (class "Default")
      (node (ref "SW1") (pin "P$2") (pinfunction "P$2_P$2") (pintype "passive"))
    )
    (net (code "88") (name "unconnected-(U$3-ACBUS0-Pad22)") (class "Default")
      (node (ref "U$3") (pin "22") (pinfunction "ACBUS0_22") (pintype "bidirectional"))
    )
    (net (code "89") (name "unconnected-(U$3-ACBUS1-Pad23)") (class "Default")
      (node (ref "U$3") (pin "23") (pinfunction "ACBUS1_23") (pintype "bidirectional"))
    )
    (net (code "90") (name "unconnected-(U$3-ACBUS2-Pad24)") (class "Default")
      (node (ref "U$3") (pin "24") (pinfunction "ACBUS2_24") (pintype "bidirectional"))
    )
    (net (code "91") (name "unconnected-(U$3-ACBUS3-Pad25)") (class "Default")
      (node (ref "U$3") (pin "25") (pinfunction "ACBUS3_25") (pintype "bidirectional"))
    )
    (net (code "92") (name "unconnected-(U$3-ACBUS4-Pad26)") (class "Default")
      (node (ref "U$3") (pin "26") (pinfunction "ACBUS4_26") (pintype "bidirectional"))
    )
    (net (code "93") (name "unconnected-(U$3-ACBUS5-Pad27)") (class "Default")
      (node (ref "U$3") (pin "27") (pinfunction "ACBUS5_27") (pintype "bidirectional"))
    )
    (net (code "94") (name "unconnected-(U$3-ACBUS6-Pad28)") (class "Default")
      (node (ref "U$3") (pin "28") (pinfunction "ACBUS6_28") (pintype "bidirectional"))
    )
    (net (code "95") (name "unconnected-(U$3-ACBUS7-Pad29)") (class "Default")
      (node (ref "U$3") (pin "29") (pinfunction "ACBUS7_29") (pintype "bidirectional"))
    )
    (net (code "96") (name "unconnected-(U$3-ADBUS4-Pad17)") (class "Default")
      (node (ref "U$3") (pin "17") (pinfunction "ADBUS4_17") (pintype "bidirectional"))
    )
    (net (code "97") (name "unconnected-(U$3-ADBUS5-Pad18)") (class "Default")
      (node (ref "U$3") (pin "18") (pinfunction "ADBUS5_18") (pintype "bidirectional"))
    )
    (net (code "98") (name "unconnected-(U$3-ADBUS6-Pad19)") (class "Default")
      (node (ref "U$3") (pin "19") (pinfunction "ADBUS6_19") (pintype "bidirectional"))
    )
    (net (code "99") (name "unconnected-(U$3-ADBUS7-Pad20)") (class "Default")
      (node (ref "U$3") (pin "20") (pinfunction "ADBUS7_20") (pintype "bidirectional"))
    )
    (net (code "100") (name "unconnected-(U$3-BCBUS0-Pad42)") (class "Default")
      (node (ref "U$3") (pin "42") (pinfunction "BCBUS0_42") (pintype "bidirectional"))
    )
    (net (code "101") (name "unconnected-(U$3-BCBUS1-Pad46)") (class "Default")
      (node (ref "U$3") (pin "46") (pinfunction "BCBUS1_46") (pintype "bidirectional"))
    )
    (net (code "102") (name "unconnected-(U$3-BCBUS2-Pad47)") (class "Default")
      (node (ref "U$3") (pin "47") (pinfunction "BCBUS2_47") (pintype "bidirectional"))
    )
    (net (code "103") (name "unconnected-(U$3-BCBUS3-Pad48)") (class "Default")
      (node (ref "U$3") (pin "48") (pinfunction "BCBUS3_48") (pintype "bidirectional"))
    )
    (net (code "104") (name "unconnected-(U$3-BCBUS4-Pad49)") (class "Default")
      (node (ref "U$3") (pin "49") (pinfunction "BCBUS4_49") (pintype "bidirectional"))
    )
    (net (code "105") (name "unconnected-(U$3-BCBUS5-Pad51)") (class "Default")
      (node (ref "U$3") (pin "51") (pinfunction "BCBUS5_51") (pintype "bidirectional"))
    )
    (net (code "106") (name "unconnected-(U$3-BCBUS6-Pad52)") (class "Default")
      (node (ref "U$3") (pin "52") (pinfunction "BCBUS6_52") (pintype "bidirectional"))
    )
    (net (code "107") (name "unconnected-(U$3-BCBUS7-Pad53)") (class "Default")
      (node (ref "U$3") (pin "53") (pinfunction "BCBUS7_53") (pintype "bidirectional"))
    )
    (net (code "108") (name "unconnected-(U$3-BDBUS2-Pad34)") (class "Default")
      (node (ref "U$3") (pin "34") (pinfunction "BDBUS2_34") (pintype "bidirectional"))
    )
    (net (code "109") (name "unconnected-(U$3-BDBUS3-Pad35)") (class "Default")
      (node (ref "U$3") (pin "35") (pinfunction "BDBUS3_35") (pintype "bidirectional"))
    )
    (net (code "110") (name "unconnected-(U$3-BDBUS4-Pad37)") (class "Default")
      (node (ref "U$3") (pin "37") (pinfunction "BDBUS4_37") (pintype "bidirectional"))
    )
    (net (code "111") (name "unconnected-(U$3-BDBUS5-Pad38)") (class "Default")
      (node (ref "U$3") (pin "38") (pinfunction "BDBUS5_38") (pintype "bidirectional"))
    )
    (net (code "112") (name "unconnected-(U$3-BDBUS6-Pad39)") (class "Default")
      (node (ref "U$3") (pin "39") (pinfunction "BDBUS6_39") (pintype "bidirectional"))
    )
    (net (code "113") (name "unconnected-(U$3-BDBUS7-Pad40)") (class "Default")
      (node (ref "U$3") (pin "40") (pinfunction "BDBUS7_40") (pintype "bidirectional"))
    )
    (net (code "114") (name "unconnected-(U$3-EECS-Pad1)") (class "Default")
      (node (ref "U$3") (pin "1") (pinfunction "EECS_1") (pintype "output"))
    )
    (net (code "115") (name "unconnected-(U$3-EEDATA-Pad55)") (class "Default")
      (node (ref "U$3") (pin "55") (pinfunction "EEDATA_55") (pintype "input"))
    )
    (net (code "116") (name "unconnected-(U$3-EESK-Pad56)") (class "Default")
      (node (ref "U$3") (pin "56") (pinfunction "EESK_56") (pintype "output"))
    )
    (net (code "117") (name "unconnected-(U$3-PWREN-Pad54)") (class "Default")
      (node (ref "U$3") (pin "54") (pinfunction "PWREN_54") (pintype "bidirectional"))
    )
    (net (code "118") (name "unconnected-(U$3-SUSPEND-Pad30)") (class "Default")
      (node (ref "U$3") (pin "30") (pinfunction "SUSPEND_30") (pintype "bidirectional"))
    )
    (net (code "119") (name "unconnected-(U$3-XTOUT-Pad4)") (class "Default")
      (node (ref "U$3") (pin "4") (pinfunction "XTOUT_4") (pintype "output"))
    )
    (net (code "120") (name "unconnected-(U$4-PA0-Pad7)") (class "Default")
      (node (ref "U$4") (pin "7") (pinfunction "PA0_7") (pintype "bidirectional"))
    )
    (net (code "121") (name "unconnected-(U$7-CLKIN-Pad10)") (class "Default")
      (node (ref "U$7") (pin "10") (pinfunction "CLKIN_10") (pintype "bidirectional"))
    )
    (net (code "122") (name "unconnected-(U$7-GPO-Pad26)") (class "Default")
      (node (ref "U$7") (pin "26") (pinfunction "GPO_26") (pintype "bidirectional"))
    )
    (net (code "123") (name "unconnected-(U$7-PGOOD-Pad27)") (class "Default")
      (node (ref "U$7") (pin "27") (pinfunction "PGOOD_27") (pintype "bidirectional"))
    )
    (net (code "124") (name "unconnected-(U1-GND-Pad4)") (class "Default")
      (node (ref "U1") (pin "4") (pinfunction "GND_4") (pintype "bidirectional"))
    )
    (net (code "125") (name "unconnected-(U1-VCC-Pad8)") (class "Default")
      (node (ref "U1") (pin "8") (pinfunction "VCC_8") (pintype "bidirectional"))
    )
  )
)
